# sb3.net
KiCad netlist of a schematic drawn in EAGLE
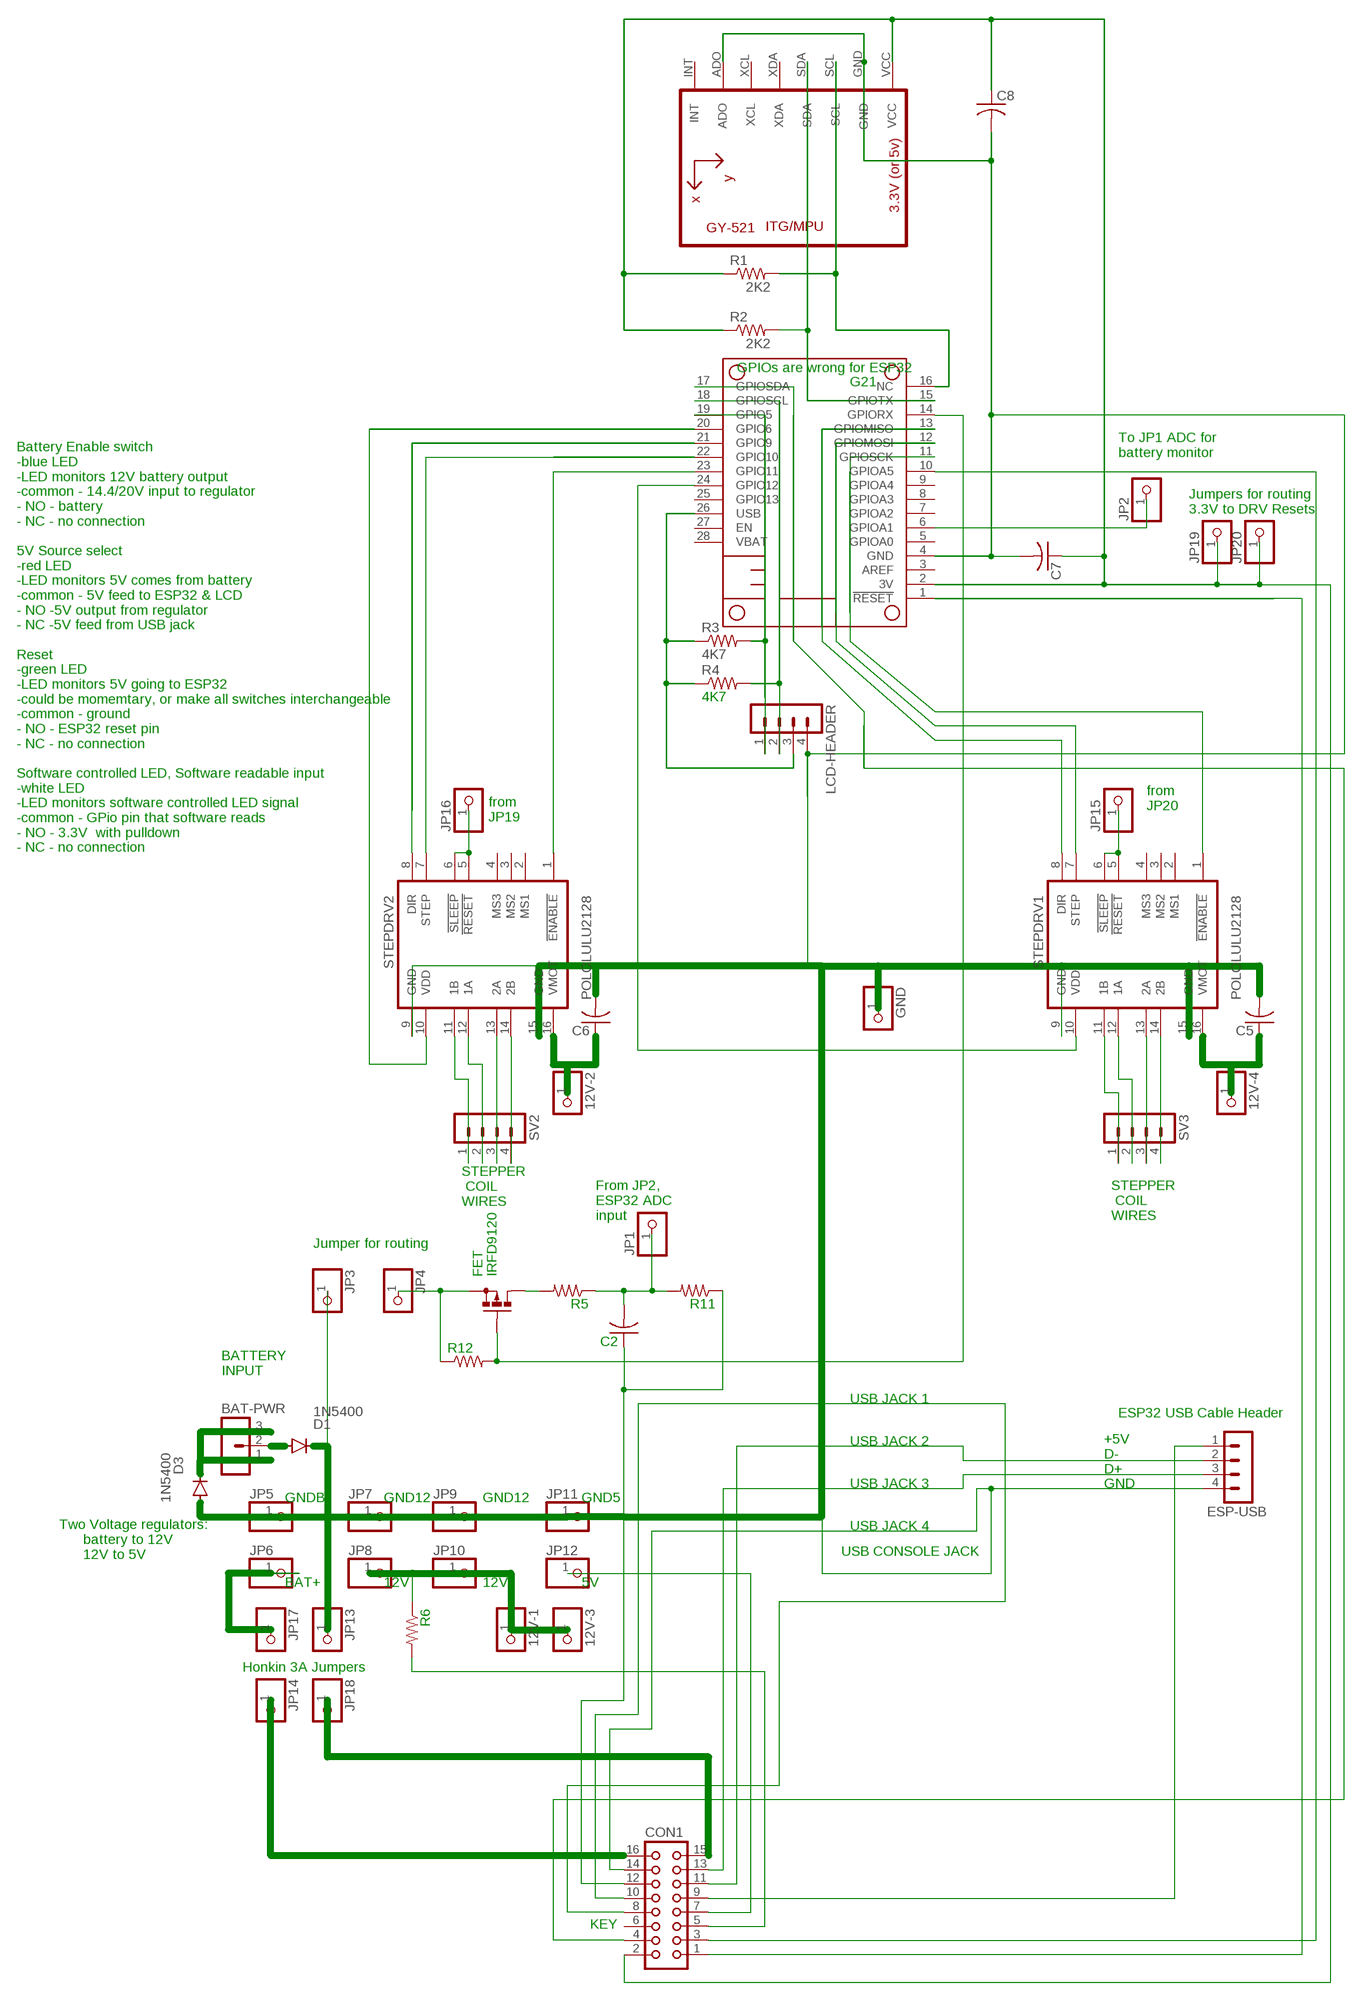
[diagram p0: schematic, sheet 1]

(export (version "E")
  (design (tool "Eeschema 10.0.6"))
  (components
    (comp (ref "12V-1")
      (value "PINHD-1X1")
      (footprint "eagle-import:1X01")
      (libsource (lib "eagle-import") (part "PINHD-1X1"))
    )
    (comp (ref "12V-2")
      (value "PINHD-1X1")
      (footprint "eagle-import:1X01")
      (libsource (lib "eagle-import") (part "PINHD-1X1"))
    )
    (comp (ref "12V-3")
      (value "PINHD-1X1")
      (footprint "eagle-import:1X01")
      (libsource (lib "eagle-import") (part "PINHD-1X1"))
    )
    (comp (ref "12V-4")
      (value "PINHD-1X1")
      (footprint "eagle-import:1X01")
      (libsource (lib "eagle-import") (part "PINHD-1X1"))
    )
    (comp (ref "BAT-PWR")
      (value "MA03-1")
      (footprint "eagle-import:MA03-1")
      (libsource (lib "eagle-import") (part "MA03-1"))
    )
    (comp (ref "C2")
      (value "C-US050-025X075")
      (footprint "eagle-import:C050-025X075")
      (libsource (lib "eagle-import") (part "C-US050-025X075"))
    )
    (comp (ref "C5")
      (value "C-US050-024X044")
      (footprint "eagle-import:C050-024X044")
      (libsource (lib "eagle-import") (part "C-US050-024X044"))
    )
    (comp (ref "C6")
      (value "C-US050-024X044")
      (footprint "eagle-import:C050-024X044")
      (libsource (lib "eagle-import") (part "C-US050-024X044"))
    )
    (comp (ref "C7")
      (value "C-US050-024X044")
      (footprint "eagle-import:C050-024X044")
      (libsource (lib "eagle-import") (part "C-US050-024X044"))
    )
    (comp (ref "C8")
      (value "C-US050-024X044")
      (footprint "eagle-import:C050-024X044")
      (libsource (lib "eagle-import") (part "C-US050-024X044"))
    )
    (comp (ref "CON1")
      (value "CON16")
      (footprint "eagle-import:CON16")
      (libsource (lib "eagle-import") (part "CON16"))
    )
    (comp (ref "D1")
      (value "1N5400")
      (footprint "eagle-import:DO201-15")
      (libsource (lib "eagle-import") (part "1N5400"))
    )
    (comp (ref "D3")
      (value "1N5400")
      (footprint "eagle-import:DO201-15")
      (libsource (lib "eagle-import") (part "1N5400"))
    )
    (comp (ref "ESP-USB")
      (value "MA04-1")
      (footprint "eagle-import:MA04-1")
      (libsource (lib "eagle-import") (part "MA04-1"))
    )
    (comp (ref "FET")
      (value "IRFD9120")
      (footprint "eagle-import:C370-01")
      (libsource (lib "eagle-import") (part "IRFD9120"))
    )
    (comp (ref "GND")
      (value "PINHD-1X1")
      (footprint "eagle-import:1X01")
      (libsource (lib "eagle-import") (part "PINHD-1X1"))
    )
    (comp (ref "JP1")
      (value "PINHD-1X1")
      (footprint "eagle-import:1X01")
      (libsource (lib "eagle-import") (part "PINHD-1X1"))
    )
    (comp (ref "JP2")
      (value "PINHD-1X1")
      (footprint "eagle-import:1X01")
      (libsource (lib "eagle-import") (part "PINHD-1X1"))
    )
    (comp (ref "JP3")
      (value "PINHD-1X1")
      (footprint "eagle-import:1X01")
      (libsource (lib "eagle-import") (part "PINHD-1X1"))
    )
    (comp (ref "JP4")
      (value "PINHD-1X1")
      (footprint "eagle-import:1X01")
      (libsource (lib "eagle-import") (part "PINHD-1X1"))
    )
    (comp (ref "JP5")
      (value "PINHD-1X1")
      (footprint "eagle-import:1X01")
      (libsource (lib "eagle-import") (part "PINHD-1X1"))
    )
    (comp (ref "JP6")
      (value "PINHD-1X1")
      (footprint "eagle-import:1X01")
      (libsource (lib "eagle-import") (part "PINHD-1X1"))
    )
    (comp (ref "JP7")
      (value "PINHD-1X1")
      (footprint "eagle-import:1X01")
      (libsource (lib "eagle-import") (part "PINHD-1X1"))
    )
    (comp (ref "JP8")
      (value "PINHD-1X1")
      (footprint "eagle-import:1X01")
      (libsource (lib "eagle-import") (part "PINHD-1X1"))
    )
    (comp (ref "JP9")
      (value "PINHD-1X1")
      (footprint "eagle-import:1X01")
      (libsource (lib "eagle-import") (part "PINHD-1X1"))
    )
    (comp (ref "JP10")
      (value "PINHD-1X1")
      (footprint "eagle-import:1X01")
      (libsource (lib "eagle-import") (part "PINHD-1X1"))
    )
    (comp (ref "JP11")
      (value "PINHD-1X1")
      (footprint "eagle-import:1X01")
      (libsource (lib "eagle-import") (part "PINHD-1X1"))
    )
    (comp (ref "JP12")
      (value "PINHD-1X1")
      (footprint "eagle-import:1X01")
      (libsource (lib "eagle-import") (part "PINHD-1X1"))
    )
    (comp (ref "JP13")
      (value "PINHD-1X1")
      (footprint "eagle-import:1X01")
      (libsource (lib "eagle-import") (part "PINHD-1X1"))
    )
    (comp (ref "JP14")
      (value "PINHD-1X1")
      (footprint "eagle-import:1X01")
      (libsource (lib "eagle-import") (part "PINHD-1X1"))
    )
    (comp (ref "JP15")
      (value "PINHD-1X1")
      (footprint "eagle-import:1X01")
      (libsource (lib "eagle-import") (part "PINHD-1X1"))
    )
    (comp (ref "JP16")
      (value "PINHD-1X1")
      (footprint "eagle-import:1X01")
      (libsource (lib "eagle-import") (part "PINHD-1X1"))
    )
    (comp (ref "JP17")
      (value "PINHD-1X1")
      (footprint "eagle-import:1X01")
      (libsource (lib "eagle-import") (part "PINHD-1X1"))
    )
    (comp (ref "JP18")
      (value "PINHD-1X1")
      (footprint "eagle-import:1X01")
      (libsource (lib "eagle-import") (part "PINHD-1X1"))
    )
    (comp (ref "JP19")
      (value "PINHD-1X1")
      (footprint "eagle-import:1X01")
      (libsource (lib "eagle-import") (part "PINHD-1X1"))
    )
    (comp (ref "JP20")
      (value "PINHD-1X1")
      (footprint "eagle-import:1X01")
      (libsource (lib "eagle-import") (part "PINHD-1X1"))
    )
    (comp (ref "LCD-HEADER")
      (value "MA04-1")
      (footprint "eagle-import:MA04-1")
      (libsource (lib "eagle-import") (part "MA04-1"))
    )
    (comp (ref "MS2")
      (value "FEATHERWING_NOHOLES")
      (footprint "eagle-import:FEATHERWING_NOHOLES")
      (libsource (lib "eagle-import") (part "FEATHERWING_NOHOLES"))
    )
    (comp (ref "R1")
      (value "2K2")
      (footprint "eagle-import:0309_12")
      (libsource (lib "eagle-import") (part "resistor_348_R-US_0309/12"))
    )
    (comp (ref "R2")
      (value "2K2")
      (footprint "eagle-import:0309_12")
      (libsource (lib "eagle-import") (part "resistor_348_R-US_0309/12"))
    )
    (comp (ref "R3")
      (value "4K7")
      (footprint "eagle-import:0309_12")
      (libsource (lib "eagle-import") (part "resistor_348_R-US_0309/12"))
    )
    (comp (ref "R4")
      (value "4K7")
      (footprint "eagle-import:0309_12")
      (libsource (lib "eagle-import") (part "resistor_348_R-US_0309/12"))
    )
    (comp (ref "R5")
      (value "R-US_0207/10")
      (footprint "eagle-import:0207_10")
      (libsource (lib "eagle-import") (part "R-US_0207/10"))
    )
    (comp (ref "R6")
      (value "R-US_0207/10")
      (footprint "eagle-import:0207_10")
      (libsource (lib "eagle-import") (part "R-US_0207/10"))
    )
    (comp (ref "R11")
      (value "R-US_0207/10")
      (footprint "eagle-import:0207_10")
      (libsource (lib "eagle-import") (part "R-US_0207/10"))
    )
    (comp (ref "R12")
      (value "R-US_0207/10")
      (footprint "eagle-import:0207_10")
      (libsource (lib "eagle-import") (part "R-US_0207/10"))
    )
    (comp (ref "STEPDRV1")
      (value "POLOLULU2128")
      (footprint "eagle-import:POLOLULU2128")
      (libsource (lib "eagle-import") (part "POLOLULU2128"))
    )
    (comp (ref "STEPDRV2")
      (value "POLOLULU2128")
      (footprint "eagle-import:POLOLULU2128")
      (libsource (lib "eagle-import") (part "POLOLULU2128"))
    )
    (comp (ref "SV2")
      (value "MA04-1")
      (footprint "eagle-import:MA04-1")
      (libsource (lib "eagle-import") (part "MA04-1"))
    )
    (comp (ref "SV3")
      (value "MA04-1")
      (footprint "eagle-import:MA04-1")
      (libsource (lib "eagle-import") (part "MA04-1"))
    )
    (comp (ref "U1")
      (value "GY-521MPU6050")
      (footprint "eagle-import:GY-521")
      (libsource (lib "eagle-import") (part "GY-521MPU6050"))
    )
  )
  (nets
    (net (code "1") (name "/VBAT") (class "Default")
      (node (ref "MS2") (pin "28") (pinfunction "VBAT_28") (pintype "power_in"))
    )
    (net (code "2") (name "Net-(12V-1-Pad1)") (class "Default")
      (node (ref "12V-1") (pin "1") (pinfunction "1_1") (pintype "passive"))
      (node (ref "12V-3") (pin "1") (pinfunction "1_1") (pintype "passive"))
      (node (ref "JP10") (pin "1") (pinfunction "1_1") (pintype "passive"))
      (node (ref "JP8") (pin "1") (pinfunction "1_1") (pintype "passive"))
      (node (ref "R6") (pin "1") (pinfunction "1_1") (pintype "passive"))
    )
    (net (code "3") (name "Net-(BAT-PWR-Pad1)") (class "Default")
      (node (ref "BAT-PWR") (pin "1") (pinfunction "1_1") (pintype "passive"))
      (node (ref "BAT-PWR") (pin "3") (pinfunction "3_3") (pintype "passive"))
      (node (ref "D3") (pin "C") (pinfunction "C_C") (pintype "passive"))
    )
    (net (code "4") (name "Net-(BAT-PWR-Pad2)") (class "Default")
      (node (ref "BAT-PWR") (pin "2") (pinfunction "2_2") (pintype "passive"))
      (node (ref "D1") (pin "A") (pinfunction "A_A") (pintype "passive"))
    )
    (net (code "5") (name "Net-(C2-Pad2)") (class "Default")
      (node (ref "C2") (pin "2") (pinfunction "2_2") (pintype "passive"))
      (node (ref "JP1") (pin "1") (pinfunction "1_1") (pintype "passive"))
      (node (ref "R11") (pin "2") (pinfunction "2_2") (pintype "passive"))
      (node (ref "R5") (pin "1") (pinfunction "1_1") (pintype "passive"))
    )
    (net (code "6") (name "Net-(CON1-Pad5)") (class "Default")
      (node (ref "CON1") (pin "5") (pinfunction "5_5") (pintype "passive"))
      (node (ref "R6") (pin "2") (pinfunction "2_2") (pintype "passive"))
    )
    (net (code "7") (name "Net-(CON1-Pad7)") (class "Default")
      (node (ref "CON1") (pin "7") (pinfunction "7_7") (pintype "passive"))
      (node (ref "JP12") (pin "1") (pinfunction "1_1") (pintype "passive"))
    )
    (net (code "8") (name "Net-(CON1-Pad9)") (class "Default")
      (node (ref "CON1") (pin "9") (pinfunction "9_9") (pintype "passive"))
      (node (ref "ESP-USB") (pin "1") (pinfunction "1_1") (pintype "passive"))
    )
    (net (code "9") (name "Net-(CON1-Pad10)") (class "Default")
      (node (ref "CON1") (pin "10") (pinfunction "10_10") (pintype "passive"))
      (node (ref "CON1") (pin "8") (pinfunction "8_8") (pintype "passive"))
    )
    (net (code "10") (name "Net-(CON1-Pad11)") (class "Default")
      (node (ref "CON1") (pin "11") (pinfunction "11_11") (pintype "passive"))
      (node (ref "ESP-USB") (pin "2") (pinfunction "2_2") (pintype "passive"))
    )
    (net (code "11") (name "Net-(CON1-Pad13)") (class "Default")
      (node (ref "CON1") (pin "13") (pinfunction "13_13") (pintype "passive"))
      (node (ref "ESP-USB") (pin "3") (pinfunction "3_3") (pintype "passive"))
    )
    (net (code "12") (name "Net-(CON1-Pad15)") (class "Default")
      (node (ref "CON1") (pin "15") (pinfunction "15_15") (pintype "passive"))
      (node (ref "JP18") (pin "1") (pinfunction "1_1") (pintype "passive"))
    )
    (net (code "13") (name "Net-(CON1-Pad16)") (class "Default")
      (node (ref "CON1") (pin "16") (pinfunction "16_16") (pintype "passive"))
      (node (ref "JP14") (pin "1") (pinfunction "1_1") (pintype "passive"))
    )
    (net (code "14") (name "Net-(D1-PadC)") (class "Default")
      (node (ref "D1") (pin "C") (pinfunction "C_C") (pintype "passive"))
      (node (ref "JP13") (pin "1") (pinfunction "1_1") (pintype "passive"))
      (node (ref "JP3") (pin "1") (pinfunction "1_1") (pintype "passive"))
    )
    (net (code "15") (name "Net-(FET-D-PadD1)") (class "Default")
      (node (ref "FET") (pin "D") (pinfunction "D_D") (pintype "passive"))
      (node (ref "FET") (pin "D1") (pinfunction "D_D1") (pintype "passive"))
      (node (ref "R5") (pin "2") (pinfunction "2_2") (pintype "passive"))
    )
    (net (code "16") (name "Net-(FET-PadS)") (class "Default")
      (node (ref "FET") (pin "S") (pinfunction "S_S") (pintype "passive"))
      (node (ref "JP4") (pin "1") (pinfunction "1_1") (pintype "passive"))
      (node (ref "R12") (pin "1") (pinfunction "1_1") (pintype "passive"))
    )
    (net (code "17") (name "Net-(JP17-Pad1)") (class "Default")
      (node (ref "JP17") (pin "1") (pinfunction "1_1") (pintype "passive"))
      (node (ref "JP6") (pin "1") (pinfunction "1_1") (pintype "passive"))
    )
    (net (code "18") (name "Net-(MS2-3V)") (class "Default")
      (node (ref "C7") (pin "1") (pinfunction "1_1") (pintype "passive"))
      (node (ref "C8") (pin "1") (pinfunction "1_1") (pintype "passive"))
      (node (ref "CON1") (pin "2") (pinfunction "2_2") (pintype "passive"))
      (node (ref "JP19") (pin "1") (pinfunction "1_1") (pintype "passive"))
      (node (ref "JP20") (pin "1") (pinfunction "1_1") (pintype "passive"))
      (node (ref "MS2") (pin "2") (pinfunction "3V_2") (pintype "power_in"))
      (node (ref "R1") (pin "1") (pinfunction "1_1") (pintype "passive"))
      (node (ref "R2") (pin "1") (pinfunction "1_1") (pintype "passive"))
      (node (ref "U1") (pin "VCC") (pinfunction "VCC_VCC") (pintype "bidirectional"))
    )
    (net (code "19") (name "Net-(MS2-GND)") (class "Default")
      (node (ref "C2") (pin "1") (pinfunction "1_1") (pintype "passive"))
      (node (ref "C5") (pin "2") (pinfunction "2_2") (pintype "passive"))
      (node (ref "C6") (pin "2") (pinfunction "2_2") (pintype "passive"))
      (node (ref "C7") (pin "2") (pinfunction "2_2") (pintype "passive"))
      (node (ref "C8") (pin "2") (pinfunction "2_2") (pintype "passive"))
      (node (ref "CON1") (pin "12") (pinfunction "12_12") (pintype "passive"))
      (node (ref "CON1") (pin "14") (pinfunction "14_14") (pintype "passive"))
      (node (ref "D3") (pin "A") (pinfunction "A_A") (pintype "passive"))
      (node (ref "ESP-USB") (pin "4") (pinfunction "4_4") (pintype "passive"))
      (node (ref "GND") (pin "1") (pinfunction "1_1") (pintype "passive"))
      (node (ref "JP11") (pin "1") (pinfunction "1_1") (pintype "passive"))
      (node (ref "JP5") (pin "1") (pinfunction "1_1") (pintype "passive"))
      (node (ref "JP7") (pin "1") (pinfunction "1_1") (pintype "passive"))
      (node (ref "JP9") (pin "1") (pinfunction "1_1") (pintype "passive"))
      (node (ref "LCD-HEADER") (pin "4") (pinfunction "4_4") (pintype "passive"))
      (node (ref "MS2") (pin "4") (pinfunction "GND_4") (pintype "power_in"))
      (node (ref "R11") (pin "1") (pinfunction "1_1") (pintype "passive"))
      (node (ref "STEPDRV1") (pin "15") (pinfunction "GND_15") (pintype "power_in"))
      (node (ref "STEPDRV1") (pin "9") (pinfunction "GND_9") (pintype "power_in"))
      (node (ref "STEPDRV2") (pin "15") (pinfunction "GND_15") (pintype "power_in"))
      (node (ref "STEPDRV2") (pin "9") (pinfunction "GND_9") (pintype "power_in"))
      (node (ref "U1") (pin "ADO") (pinfunction "ADO_ADO") (pintype "bidirectional"))
      (node (ref "U1") (pin "GND") (pinfunction "GND_GND") (pintype "bidirectional"))
    )
    (net (code "20") (name "Net-(MS2-GPIO5)") (class "Default")
      (node (ref "LCD-HEADER") (pin "1") (pinfunction "1_1") (pintype "passive"))
      (node (ref "MS2") (pin "19") (pinfunction "GPIO5_19") (pintype "bidirectional"))
      (node (ref "R3") (pin "2") (pinfunction "2_2") (pintype "passive"))
    )
    (net (code "21") (name "Net-(MS2-GPIO6)") (class "Default")
      (node (ref "MS2") (pin "20") (pinfunction "GPIO6_20") (pintype "bidirectional"))
      (node (ref "STEPDRV2") (pin "10") (pinfunction "VDD_10") (pintype "power_in"))
    )
    (net (code "22") (name "Net-(MS2-GPIO9)") (class "Default")
      (node (ref "MS2") (pin "21") (pinfunction "GPIO9_21") (pintype "bidirectional"))
      (node (ref "STEPDRV2") (pin "8") (pinfunction "DIR_8") (pintype "input"))
    )
    (net (code "23") (name "Net-(MS2-GPIO10)") (class "Default")
      (node (ref "MS2") (pin "22") (pinfunction "GPIO10_22") (pintype "bidirectional"))
      (node (ref "STEPDRV2") (pin "7") (pinfunction "STEP_7") (pintype "input"))
    )
    (net (code "24") (name "Net-(MS2-GPIO11)") (class "Default")
      (node (ref "MS2") (pin "23") (pinfunction "GPIO11_23") (pintype "bidirectional"))
      (node (ref "STEPDRV2") (pin "1") (pinfunction "~{ENABLE}_1") (pintype "input"))
    )
    (net (code "25") (name "Net-(MS2-GPIO12)") (class "Default")
      (node (ref "MS2") (pin "24") (pinfunction "GPIO12_24") (pintype "bidirectional"))
      (node (ref "STEPDRV1") (pin "10") (pinfunction "VDD_10") (pintype "power_in"))
    )
    (net (code "26") (name "Net-(MS2-GPIOA1)") (class "Default")
      (node (ref "JP2") (pin "1") (pinfunction "1_1") (pintype "passive"))
      (node (ref "MS2") (pin "6") (pinfunction "GPIOA1_6") (pintype "bidirectional"))
    )
    (net (code "27") (name "Net-(MS2-GPIOA5)") (class "Default")
      (node (ref "CON1") (pin "3") (pinfunction "3_3") (pintype "passive"))
      (node (ref "MS2") (pin "10") (pinfunction "GPIOA5_10") (pintype "bidirectional"))
    )
    (net (code "28") (name "Net-(MS2-GPIOMISO)") (class "Default")
      (node (ref "MS2") (pin "13") (pinfunction "GPIOMISO_13") (pintype "bidirectional"))
      (node (ref "STEPDRV1") (pin "8") (pinfunction "DIR_8") (pintype "input"))
    )
    (net (code "29") (name "Net-(MS2-GPIOMOSI)") (class "Default")
      (node (ref "MS2") (pin "12") (pinfunction "GPIOMOSI_12") (pintype "bidirectional"))
      (node (ref "STEPDRV1") (pin "7") (pinfunction "STEP_7") (pintype "input"))
    )
    (net (code "30") (name "Net-(MS2-GPIORX)") (class "Default")
      (node (ref "FET") (pin "G") (pinfunction "G_G") (pintype "passive"))
      (node (ref "MS2") (pin "14") (pinfunction "GPIORX_14") (pintype "bidirectional"))
      (node (ref "R12") (pin "2") (pinfunction "2_2") (pintype "passive"))
    )
    (net (code "31") (name "Net-(MS2-GPIOSCK)") (class "Default")
      (node (ref "MS2") (pin "11") (pinfunction "GPIOSCK_11") (pintype "bidirectional"))
      (node (ref "STEPDRV1") (pin "1") (pinfunction "~{ENABLE}_1") (pintype "input"))
    )
    (net (code "32") (name "Net-(MS2-GPIOSCL)") (class "Default")
      (node (ref "LCD-HEADER") (pin "2") (pinfunction "2_2") (pintype "passive"))
      (node (ref "MS2") (pin "18") (pinfunction "GPIOSCL_18") (pintype "bidirectional"))
      (node (ref "R4") (pin "2") (pinfunction "2_2") (pintype "passive"))
    )
    (net (code "33") (name "Net-(MS2-GPIOSDA)") (class "Default")
      (node (ref "CON1") (pin "4") (pinfunction "4_4") (pintype "passive"))
      (node (ref "MS2") (pin "17") (pinfunction "GPIOSDA_17") (pintype "bidirectional"))
    )
    (net (code "34") (name "Net-(MS2-GPIOTX)") (class "Default")
      (node (ref "MS2") (pin "15") (pinfunction "GPIOTX_15") (pintype "bidirectional"))
      (node (ref "R2") (pin "2") (pinfunction "2_2") (pintype "passive"))
      (node (ref "U1") (pin "SDA") (pinfunction "SDA_SDA") (pintype "bidirectional"))
    )
    (net (code "35") (name "Net-(MS2-NC)") (class "Default")
      (node (ref "MS2") (pin "16") (pinfunction "NC_16") (pintype "passive"))
      (node (ref "R1") (pin "2") (pinfunction "2_2") (pintype "passive"))
      (node (ref "U1") (pin "SCL") (pinfunction "SCL_SCL") (pintype "bidirectional"))
    )
    (net (code "36") (name "Net-(MS2-USB)") (class "Default")
      (node (ref "LCD-HEADER") (pin "3") (pinfunction "3_3") (pintype "passive"))
      (node (ref "MS2") (pin "26") (pinfunction "USB_26") (pintype "power_in"))
      (node (ref "R3") (pin "1") (pinfunction "1_1") (pintype "passive"))
      (node (ref "R4") (pin "1") (pinfunction "1_1") (pintype "passive"))
    )
    (net (code "37") (name "Net-(MS2-~{RESET})") (class "Default")
      (node (ref "CON1") (pin "1") (pinfunction "1_1") (pintype "passive"))
      (node (ref "MS2") (pin "1") (pinfunction "~{RESET}_1") (pintype "input"))
    )
    (net (code "38") (name "Net-(STEPDRV1-1A)") (class "Default")
      (node (ref "STEPDRV1") (pin "12") (pinfunction "1A_12") (pintype "output"))
      (node (ref "SV3") (pin "2") (pinfunction "2_2") (pintype "passive"))
    )
    (net (code "39") (name "Net-(STEPDRV1-1B)") (class "Default")
      (node (ref "STEPDRV1") (pin "11") (pinfunction "1B_11") (pintype "output"))
      (node (ref "SV3") (pin "1") (pinfunction "1_1") (pintype "passive"))
    )
    (net (code "40") (name "Net-(STEPDRV1-2A)") (class "Default")
      (node (ref "STEPDRV1") (pin "13") (pinfunction "2A_13") (pintype "output"))
      (node (ref "SV3") (pin "3") (pinfunction "3_3") (pintype "passive"))
    )
    (net (code "41") (name "Net-(STEPDRV1-2B)") (class "Default")
      (node (ref "STEPDRV1") (pin "14") (pinfunction "2B_14") (pintype "output"))
      (node (ref "SV3") (pin "4") (pinfunction "4_4") (pintype "passive"))
    )
    (net (code "42") (name "Net-(STEPDRV1-VMOT)") (class "Default")
      (node (ref "12V-4") (pin "1") (pinfunction "1_1") (pintype "passive"))
      (node (ref "C5") (pin "1") (pinfunction "1_1") (pintype "passive"))
      (node (ref "STEPDRV1") (pin "16") (pinfunction "VMOT_16") (pintype "power_in"))
    )
    (net (code "43") (name "Net-(STEPDRV1-~{RESET})") (class "Default")
      (node (ref "JP15") (pin "1") (pinfunction "1_1") (pintype "passive"))
      (node (ref "STEPDRV1") (pin "5") (pinfunction "~{RESET}_5") (pintype "input"))
      (node (ref "STEPDRV1") (pin "6") (pinfunction "~{SLEEP}_6") (pintype "input"))
    )
    (net (code "44") (name "Net-(STEPDRV2-1A)") (class "Default")
      (node (ref "STEPDRV2") (pin "12") (pinfunction "1A_12") (pintype "output"))
      (node (ref "SV2") (pin "2") (pinfunction "2_2") (pintype "passive"))
    )
    (net (code "45") (name "Net-(STEPDRV2-1B)") (class "Default")
      (node (ref "STEPDRV2") (pin "11") (pinfunction "1B_11") (pintype "output"))
      (node (ref "SV2") (pin "1") (pinfunction "1_1") (pintype "passive"))
    )
    (net (code "46") (name "Net-(STEPDRV2-2A)") (class "Default")
      (node (ref "STEPDRV2") (pin "13") (pinfunction "2A_13") (pintype "output"))
      (node (ref "SV2") (pin "3") (pinfunction "3_3") (pintype "passive"))
    )
    (net (code "47") (name "Net-(STEPDRV2-2B)") (class "Default")
      (node (ref "STEPDRV2") (pin "14") (pinfunction "2B_14") (pintype "output"))
      (node (ref "SV2") (pin "4") (pinfunction "4_4") (pintype "passive"))
    )
    (net (code "48") (name "Net-(STEPDRV2-VMOT)") (class "Default")
      (node (ref "12V-2") (pin "1") (pinfunction "1_1") (pintype "passive"))
      (node (ref "C6") (pin "1") (pinfunction "1_1") (pintype "passive"))
      (node (ref "STEPDRV2") (pin "16") (pinfunction "VMOT_16") (pintype "power_in"))
    )
    (net (code "49") (name "Net-(STEPDRV2-~{RESET})") (class "Default")
      (node (ref "JP16") (pin "1") (pinfunction "1_1") (pintype "passive"))
      (node (ref "STEPDRV2") (pin "5") (pinfunction "~{RESET}_5") (pintype "input"))
      (node (ref "STEPDRV2") (pin "6") (pinfunction "~{SLEEP}_6") (pintype "input"))
    )
    (net (code "50") (name "unconnected-(CON1-Pad6)") (class "Default")
      (node (ref "CON1") (pin "6") (pinfunction "6_6") (pintype "passive"))
    )
    (net (code "51") (name "unconnected-(MS2-AREF-Pad3)") (class "Default")
      (node (ref "MS2") (pin "3") (pinfunction "AREF_3") (pintype "passive"))
    )
    (net (code "52") (name "unconnected-(MS2-EN-Pad27)") (class "Default")
      (node (ref "MS2") (pin "27") (pinfunction "EN_27") (pintype "passive"))
    )
    (net (code "53") (name "unconnected-(MS2-GPIO13-Pad25)") (class "Default")
      (node (ref "MS2") (pin "25") (pinfunction "GPIO13_25") (pintype "bidirectional"))
    )
    (net (code "54") (name "unconnected-(MS2-GPIOA0-Pad5)") (class "Default")
      (node (ref "MS2") (pin "5") (pinfunction "GPIOA0_5") (pintype "bidirectional"))
    )
    (net (code "55") (name "unconnected-(MS2-GPIOA2-Pad7)") (class "Default")
      (node (ref "MS2") (pin "7") (pinfunction "GPIOA2_7") (pintype "bidirectional"))
    )
    (net (code "56") (name "unconnected-(MS2-GPIOA3-Pad8)") (class "Default")
      (node (ref "MS2") (pin "8") (pinfunction "GPIOA3_8") (pintype "bidirectional"))
    )
    (net (code "57") (name "unconnected-(MS2-GPIOA4-Pad9)") (class "Default")
      (node (ref "MS2") (pin "9") (pinfunction "GPIOA4_9") (pintype "bidirectional"))
    )
    (net (code "58") (name "unconnected-(STEPDRV1-MS1-Pad2)") (class "Default")
      (node (ref "STEPDRV1") (pin "2") (pinfunction "MS1_2") (pintype "input"))
    )
    (net (code "59") (name "unconnected-(STEPDRV1-MS2-Pad3)") (class "Default")
      (node (ref "STEPDRV1") (pin "3") (pinfunction "MS2_3") (pintype "input"))
    )
    (net (code "60") (name "unconnected-(STEPDRV1-MS3-Pad4)") (class "Default")
      (node (ref "STEPDRV1") (pin "4") (pinfunction "MS3_4") (pintype "input"))
    )
    (net (code "61") (name "unconnected-(STEPDRV2-MS1-Pad2)") (class "Default")
      (node (ref "STEPDRV2") (pin "2") (pinfunction "MS1_2") (pintype "input"))
    )
    (net (code "62") (name "unconnected-(STEPDRV2-MS2-Pad3)") (class "Default")
      (node (ref "STEPDRV2") (pin "3") (pinfunction "MS2_3") (pintype "input"))
    )
    (net (code "63") (name "unconnected-(STEPDRV2-MS3-Pad4)") (class "Default")
      (node (ref "STEPDRV2") (pin "4") (pinfunction "MS3_4") (pintype "input"))
    )
    (net (code "64") (name "unconnected-(U1-PadINT)") (class "Default")
      (node (ref "U1") (pin "INT") (pinfunction "INT_INT") (pintype "bidirectional"))
    )
    (net (code "65") (name "unconnected-(U1-PadXCL)") (class "Default")
      (node (ref "U1") (pin "XCL") (pinfunction "XCL_XCL") (pintype "bidirectional"))
    )
    (net (code "66") (name "unconnected-(U1-PadXDA)") (class "Default")
      (node (ref "U1") (pin "XDA") (pinfunction "XDA_XDA") (pintype "bidirectional"))
    )
  )
)
